# 1-Schematic_CessnaCitationX_APU.net
KiCad netlist of a schematic drawn in EasyEDA
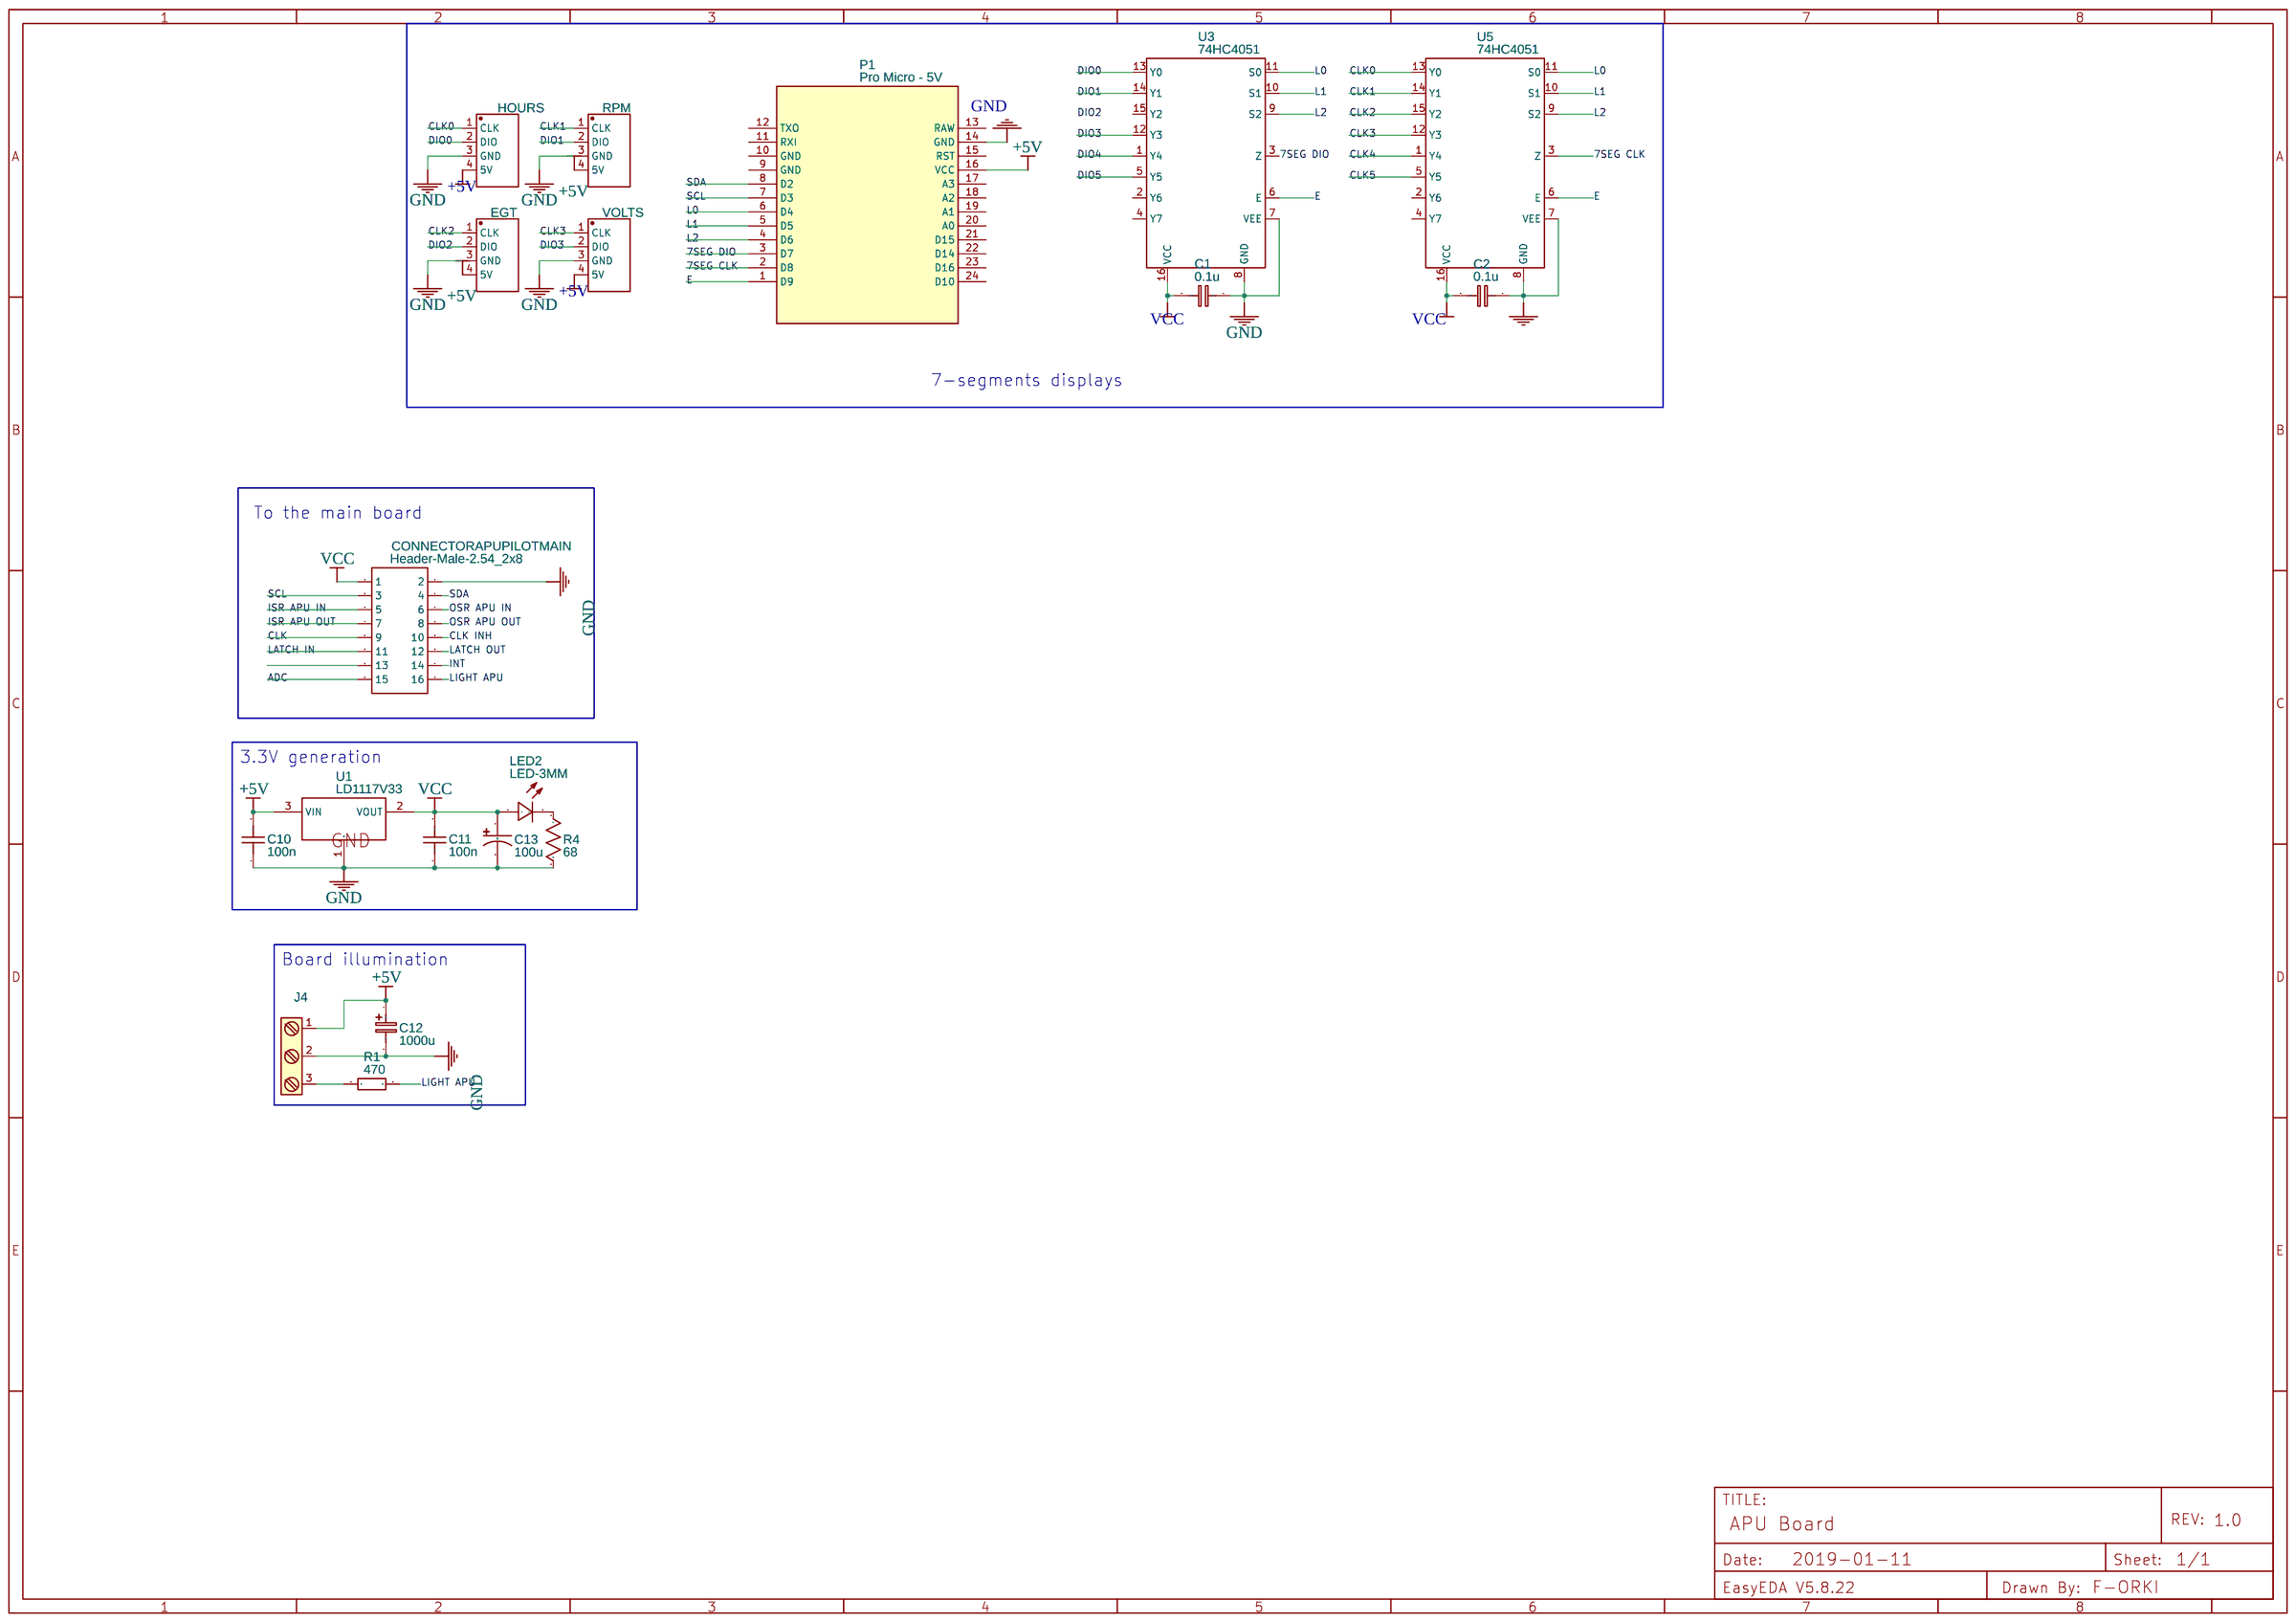
[diagram p0: schematic sheet]

(export (version "E")
  (design (tool "Eeschema 10.0.6"))
  (components
    (comp (ref "C1")
      (value "0.1u")
      (fields (field (name "BOM_Manufacturer Part") "?"))
      (libsource (lib "") (part "Cap_RAD-0.1_EU"))
    )
    (comp (ref "C2")
      (value "0.1u")
      (fields (field (name "BOM_Manufacturer Part") "?"))
      (libsource (lib "") (part "Cap_RAD-0.1_EU"))
    )
    (comp (ref "C10")
      (value "100n")
      (fields (field (name "BOM_Manufacturer Part") "?"))
      (libsource (lib "") (part "Cap_RAD-0.1_US"))
    )
    (comp (ref "C11")
      (value "100n")
      (fields (field (name "BOM_Manufacturer Part") "?"))
      (libsource (lib "") (part "Cap_RAD-0.1_US"))
    )
    (comp (ref "C12")
      (value "1000u")
      (fields (field (name "BOM_Manufacturer Part") "?"))
      (libsource (lib "") (part "Cap_Electrolytic(TH)_D3.0XF1.5_EU"))
    )
    (comp (ref "C13")
      (value "100u")
      (fields (field (name "BOM_Manufacturer Part") "?"))
      (libsource (lib "") (part "Cap_Electrolytic(TH)_D3.0XF1.5_US"))
    )
    (comp (ref "CONNECTORAPUPILOTMAIN")
      (value "Header-Male-2.54_2x8")
      (fields
        (field (name "BOM_Manufacturer Part") "Double row straight 2*8Headers  Pins 2.54mm")
        (field (name "BOM_Supplier Part") "C68234")
      )
      (libsource (lib "") (part "Unknown_280_445"))
    )
    (comp (ref "EGT")
      (value "7seg display module TM1637")
      (fields
        (field (name "BOM_Manufacturer Part") "WJ2EDGVC-5.08-4P")
        (field (name "BOM_Supplier Part") "C8471")
      )
      (libsource (lib "") (part "Unknown_340_175"))
    )
    (comp (ref "HOURS")
      (value "7seg display module TM1637")
      (fields
        (field (name "BOM_Manufacturer Part") "WJ2EDGVC-5.08-4P")
        (field (name "BOM_Supplier Part") "C8471")
      )
      (libsource (lib "") (part "Unknown_340_100"))
    )
    (comp (ref "J4")
      (value "Screw_Terminal_1x03")
      (fields (field (name "BOM_Manufacturer Part") "?"))
      (libsource (lib "") (part "Unknown_210_750"))
    )
    (comp (ref "LED2")
      (value "LED-3MM")
      (fields
        (field (name "BOM_Manufacturer Part") "204-10SURD/S530-A3")
        (field (name "BOM_Supplier Part") "C99772")
      )
      (libsource (lib "") (part "Unknown_370_570"))
    )
    (comp (ref "P1")
      (value "Pro Micro - 5V")
      (fields (field (name "BOM_Manufacturer Part") "?"))
      (libsource (lib "") (part "Unknown_615_140"))
    )
    (comp (ref "R1")
      (value "470")
      (fields (field (name "BOM_Manufacturer Part") "?"))
      (libsource (lib "") (part "Res_AXIAL-0.3(1/8W)_EU"))
    )
    (comp (ref "R4")
      (value "68")
      (fields (field (name "BOM_Manufacturer Part") "?"))
      (libsource (lib "") (part "Res_AXIAL-0.3(1/8W)_US"))
    )
    (comp (ref "RPM")
      (value "7seg display module TM1637")
      (fields
        (field (name "BOM_Manufacturer Part") "WJ2EDGVC-5.08-4P")
        (field (name "BOM_Supplier Part") "C8471")
      )
      (libsource (lib "") (part "Unknown_420_100"))
    )
    (comp (ref "U1")
      (value "LD1117V33")
      (fields (field (name "BOM_Supplier Part") "C283467"))
      (libsource (lib "") (part "Unknown_240_595"))
    )
    (comp (ref "U3")
      (value "74HC4051")
      (fields (field (name "BOM_Manufacturer Part") "?"))
      (libsource (lib "") (part "Unknown_860_105"))
    )
    (comp (ref "U5")
      (value "74HC4051")
      (fields (field (name "BOM_Manufacturer Part") "?"))
      (libsource (lib "") (part "Unknown_1060_105"))
    )
    (comp (ref "VOLTS")
      (value "7seg display module TM1637")
      (fields
        (field (name "BOM_Manufacturer Part") "WJ2EDGVC-5.08-4P")
        (field (name "BOM_Supplier Part") "C8471")
      )
      (libsource (lib "") (part "Unknown_420_175"))
    )
  )
  (nets
    (net (code "1") (name "+5V") (class "Default")
      (node (ref "C10") (pin "2") (pinfunction "2_2") (pintype "unspecified"))
      (node (ref "C12") (pin "1") (pinfunction "1_1") (pintype "unspecified"))
      (node (ref "EGT") (pin "4") (pinfunction "5V_4") (pintype "unspecified"))
      (node (ref "HOURS") (pin "4") (pinfunction "5V_4") (pintype "unspecified"))
      (node (ref "J4") (pin "1") (pintype "unspecified"))
      (node (ref "P1") (pin "16") (pinfunction "VCC_16") (pintype "unspecified"))
      (node (ref "RPM") (pin "4") (pinfunction "5V_4") (pintype "unspecified"))
      (node (ref "U1") (pin "3") (pinfunction "VIN_3") (pintype "passive"))
      (node (ref "VOLTS") (pin "4") (pinfunction "5V_4") (pintype "unspecified"))
    )
    (net (code "2") (name "/7SEG CLK") (class "Default")
      (node (ref "P1") (pin "2") (pinfunction "D8_2") (pintype "unspecified"))
      (node (ref "U5") (pin "3") (pinfunction "Z_3") (pintype "unspecified"))
    )
    (net (code "3") (name "/7SEG DIO") (class "Default")
      (node (ref "P1") (pin "3") (pinfunction "D7_3") (pintype "unspecified"))
      (node (ref "U3") (pin "3") (pinfunction "Z_3") (pintype "unspecified"))
    )
    (net (code "4") (name "/ADC") (class "Default")
      (node (ref "CONNECTORAPUPILOTMAIN") (pin "15") (pinfunction "15_15") (pintype "input"))
    )
    (net (code "5") (name "/CLK") (class "Default")
      (node (ref "CONNECTORAPUPILOTMAIN") (pin "9") (pinfunction "9_9") (pintype "input"))
    )
    (net (code "6") (name "/CLK INH") (class "Default")
      (node (ref "CONNECTORAPUPILOTMAIN") (pin "10") (pinfunction "10_10") (pintype "input"))
    )
    (net (code "7") (name "/CLK0") (class "Default")
      (node (ref "HOURS") (pin "1") (pinfunction "CLK_1") (pintype "unspecified"))
      (node (ref "U5") (pin "13") (pinfunction "Y0_13") (pintype "unspecified"))
    )
    (net (code "8") (name "/CLK1") (class "Default")
      (node (ref "RPM") (pin "1") (pinfunction "CLK_1") (pintype "unspecified"))
      (node (ref "U5") (pin "14") (pinfunction "Y1_14") (pintype "unspecified"))
    )
    (net (code "9") (name "/CLK2") (class "Default")
      (node (ref "EGT") (pin "1") (pinfunction "CLK_1") (pintype "unspecified"))
      (node (ref "U5") (pin "15") (pinfunction "Y2_15") (pintype "unspecified"))
    )
    (net (code "10") (name "/CLK3") (class "Default")
      (node (ref "U5") (pin "12") (pinfunction "Y3_12") (pintype "unspecified"))
      (node (ref "VOLTS") (pin "1") (pinfunction "CLK_1") (pintype "unspecified"))
    )
    (net (code "11") (name "/CLK4") (class "Default")
      (node (ref "U5") (pin "1") (pinfunction "Y4_1") (pintype "unspecified"))
    )
    (net (code "12") (name "/CLK5") (class "Default")
      (node (ref "U5") (pin "5") (pinfunction "Y5_5") (pintype "unspecified"))
    )
    (net (code "13") (name "/DIO0") (class "Default")
      (node (ref "HOURS") (pin "2") (pinfunction "DIO_2") (pintype "unspecified"))
      (node (ref "U3") (pin "13") (pinfunction "Y0_13") (pintype "unspecified"))
    )
    (net (code "14") (name "/DIO1") (class "Default")
      (node (ref "RPM") (pin "2") (pinfunction "DIO_2") (pintype "unspecified"))
      (node (ref "U3") (pin "14") (pinfunction "Y1_14") (pintype "unspecified"))
    )
    (net (code "15") (name "/DIO2") (class "Default")
      (node (ref "EGT") (pin "2") (pinfunction "DIO_2") (pintype "unspecified"))
    )
    (net (code "16") (name "/DIO3") (class "Default")
      (node (ref "U3") (pin "12") (pinfunction "Y3_12") (pintype "unspecified"))
      (node (ref "VOLTS") (pin "2") (pinfunction "DIO_2") (pintype "unspecified"))
    )
    (net (code "17") (name "/DIO4") (class "Default")
      (node (ref "U3") (pin "1") (pinfunction "Y4_1") (pintype "unspecified"))
    )
    (net (code "18") (name "/DIO5") (class "Default")
      (node (ref "U3") (pin "5") (pinfunction "Y5_5") (pintype "unspecified"))
    )
    (net (code "19") (name "/E") (class "Default")
      (node (ref "P1") (pin "1") (pinfunction "D9_1") (pintype "unspecified"))
      (node (ref "U3") (pin "6") (pinfunction "E_6") (pintype "unspecified"))
      (node (ref "U5") (pin "6") (pinfunction "E_6") (pintype "unspecified"))
    )
    (net (code "20") (name "/INT") (class "Default")
      (node (ref "CONNECTORAPUPILOTMAIN") (pin "14") (pinfunction "14_14") (pintype "input"))
    )
    (net (code "21") (name "/ISR APU IN") (class "Default")
      (node (ref "CONNECTORAPUPILOTMAIN") (pin "5") (pinfunction "5_5") (pintype "input"))
    )
    (net (code "22") (name "/ISR APU OUT") (class "Default")
      (node (ref "CONNECTORAPUPILOTMAIN") (pin "7") (pinfunction "7_7") (pintype "input"))
    )
    (net (code "23") (name "/L0") (class "Default")
      (node (ref "P1") (pin "6") (pinfunction "D4_6") (pintype "unspecified"))
      (node (ref "U3") (pin "11") (pinfunction "S0_11") (pintype "unspecified"))
      (node (ref "U5") (pin "11") (pinfunction "S0_11") (pintype "unspecified"))
    )
    (net (code "24") (name "/L1") (class "Default")
      (node (ref "P1") (pin "5") (pinfunction "D5_5") (pintype "unspecified"))
      (node (ref "U3") (pin "10") (pinfunction "S1_10") (pintype "unspecified"))
      (node (ref "U5") (pin "10") (pinfunction "S1_10") (pintype "unspecified"))
    )
    (net (code "25") (name "/L2") (class "Default")
      (node (ref "P1") (pin "4") (pinfunction "D6_4") (pintype "unspecified"))
      (node (ref "U3") (pin "9") (pinfunction "S2_9") (pintype "unspecified"))
      (node (ref "U5") (pin "9") (pinfunction "S2_9") (pintype "unspecified"))
    )
    (net (code "26") (name "/LATCH IN") (class "Default")
      (node (ref "CONNECTORAPUPILOTMAIN") (pin "11") (pinfunction "11_11") (pintype "input"))
    )
    (net (code "27") (name "/LATCH OUT") (class "Default")
      (node (ref "CONNECTORAPUPILOTMAIN") (pin "12") (pinfunction "12_12") (pintype "input"))
    )
    (net (code "28") (name "/LIGHT APU") (class "Default")
      (node (ref "CONNECTORAPUPILOTMAIN") (pin "16") (pinfunction "16_16") (pintype "input"))
      (node (ref "R1") (pin "2") (pinfunction "2_2") (pintype "unspecified"))
    )
    (net (code "29") (name "/OSR APU IN") (class "Default")
      (node (ref "CONNECTORAPUPILOTMAIN") (pin "6") (pinfunction "6_6") (pintype "input"))
    )
    (net (code "30") (name "/OSR APU OUT") (class "Default")
      (node (ref "CONNECTORAPUPILOTMAIN") (pin "8") (pinfunction "8_8") (pintype "input"))
    )
    (net (code "31") (name "/SCL") (class "Default")
      (node (ref "CONNECTORAPUPILOTMAIN") (pin "3") (pinfunction "3_3") (pintype "input"))
      (node (ref "P1") (pin "7") (pinfunction "D3_7") (pintype "unspecified"))
    )
    (net (code "32") (name "/SDA") (class "Default")
      (node (ref "CONNECTORAPUPILOTMAIN") (pin "4") (pinfunction "4_4") (pintype "input"))
      (node (ref "P1") (pin "8") (pinfunction "D2_8") (pintype "unspecified"))
    )
    (net (code "33") (name "GND") (class "Default")
      (node (ref "C1") (pin "1") (pinfunction "1_1") (pintype "unspecified"))
      (node (ref "C10") (pin "1") (pinfunction "1_1") (pintype "unspecified"))
      (node (ref "C11") (pin "1") (pinfunction "1_1") (pintype "unspecified"))
      (node (ref "C12") (pin "2") (pinfunction "2_2") (pintype "unspecified"))
      (node (ref "C13") (pin "2") (pinfunction "2_2") (pintype "unspecified"))
      (node (ref "C2") (pin "1") (pinfunction "1_1") (pintype "unspecified"))
      (node (ref "CONNECTORAPUPILOTMAIN") (pin "2") (pinfunction "2_2") (pintype "input"))
      (node (ref "EGT") (pin "3") (pinfunction "GND_3") (pintype "unspecified"))
      (node (ref "HOURS") (pin "3") (pinfunction "GND_3") (pintype "unspecified"))
      (node (ref "J4") (pin "2") (pintype "unspecified"))
      (node (ref "P1") (pin "14") (pinfunction "GND_14") (pintype "unspecified"))
      (node (ref "R4") (pin "2") (pinfunction "2_2") (pintype "unspecified"))
      (node (ref "RPM") (pin "3") (pinfunction "GND_3") (pintype "unspecified"))
      (node (ref "U1") (pin "1") (pinfunction "GND_1") (pintype "unspecified"))
      (node (ref "U3") (pin "7") (pinfunction "VEE_7") (pintype "unspecified"))
      (node (ref "U3") (pin "8") (pinfunction "GND_8") (pintype "unspecified"))
      (node (ref "U5") (pin "7") (pinfunction "VEE_7") (pintype "unspecified"))
      (node (ref "U5") (pin "8") (pinfunction "GND_8") (pintype "unspecified"))
      (node (ref "VOLTS") (pin "3") (pinfunction "GND_3") (pintype "unspecified"))
    )
    (net (code "34") (name "Net-(J4-Pad3)") (class "Default")
      (node (ref "J4") (pin "3") (pintype "unspecified"))
      (node (ref "R1") (pin "1") (pinfunction "1_1") (pintype "unspecified"))
    )
    (net (code "35") (name "Net-(LED2--)") (class "Default")
      (node (ref "LED2") (pin "2") (pinfunction "-_2") (pintype "unspecified"))
      (node (ref "R4") (pin "1") (pinfunction "1_1") (pintype "unspecified"))
    )
    (net (code "36") (name "VCC") (class "Default")
      (node (ref "C1") (pin "2") (pinfunction "2_2") (pintype "unspecified"))
      (node (ref "C11") (pin "2") (pinfunction "2_2") (pintype "unspecified"))
      (node (ref "C13") (pin "1") (pinfunction "1_1") (pintype "unspecified"))
      (node (ref "C2") (pin "2") (pinfunction "2_2") (pintype "unspecified"))
      (node (ref "CONNECTORAPUPILOTMAIN") (pin "1") (pinfunction "1_1") (pintype "input"))
      (node (ref "LED2") (pin "1") (pinfunction "+_1") (pintype "unspecified"))
      (node (ref "U1") (pin "2") (pinfunction "VOUT_2") (pintype "passive"))
      (node (ref "U3") (pin "16") (pinfunction "VCC_16") (pintype "unspecified"))
      (node (ref "U5") (pin "16") (pinfunction "VCC_16") (pintype "unspecified"))
    )
    (net (code "37") (name "unconnected-(CONNECTORAPUPILOTMAIN-Pad13)") (class "Default")
      (node (ref "CONNECTORAPUPILOTMAIN") (pin "13") (pinfunction "13_13") (pintype "input"))
    )
    (net (code "38") (name "unconnected-(P1-A0-Pad20)") (class "Default")
      (node (ref "P1") (pin "20") (pinfunction "A0_20") (pintype "unspecified"))
    )
    (net (code "39") (name "unconnected-(P1-A1-Pad19)") (class "Default")
      (node (ref "P1") (pin "19") (pinfunction "A1_19") (pintype "unspecified"))
    )
    (net (code "40") (name "unconnected-(P1-A2-Pad18)") (class "Default")
      (node (ref "P1") (pin "18") (pinfunction "A2_18") (pintype "unspecified"))
    )
    (net (code "41") (name "unconnected-(P1-A3-Pad17)") (class "Default")
      (node (ref "P1") (pin "17") (pinfunction "A3_17") (pintype "unspecified"))
    )
    (net (code "42") (name "unconnected-(P1-D10-Pad24)") (class "Default")
      (node (ref "P1") (pin "24") (pinfunction "D10_24") (pintype "unspecified"))
    )
    (net (code "43") (name "unconnected-(P1-D14-Pad22)") (class "Default")
      (node (ref "P1") (pin "22") (pinfunction "D14_22") (pintype "unspecified"))
    )
    (net (code "44") (name "unconnected-(P1-D15-Pad21)") (class "Default")
      (node (ref "P1") (pin "21") (pinfunction "D15_21") (pintype "unspecified"))
    )
    (net (code "45") (name "unconnected-(P1-D16-Pad23)") (class "Default")
      (node (ref "P1") (pin "23") (pinfunction "D16_23") (pintype "unspecified"))
    )
    (net (code "46") (name "unconnected-(P1-GND-Pad9)") (class "Default")
      (node (ref "P1") (pin "9") (pinfunction "GND_9") (pintype "unspecified"))
    )
    (net (code "47") (name "unconnected-(P1-GND-Pad10)") (class "Default")
      (node (ref "P1") (pin "10") (pinfunction "GND_10") (pintype "unspecified"))
    )
    (net (code "48") (name "unconnected-(P1-RAW-Pad13)") (class "Default")
      (node (ref "P1") (pin "13") (pinfunction "RAW_13") (pintype "unspecified"))
    )
    (net (code "49") (name "unconnected-(P1-RST-Pad15)") (class "Default")
      (node (ref "P1") (pin "15") (pinfunction "RST_15") (pintype "unspecified"))
    )
    (net (code "50") (name "unconnected-(P1-RXI-Pad11)") (class "Default")
      (node (ref "P1") (pin "11") (pinfunction "RXI_11") (pintype "unspecified"))
    )
    (net (code "51") (name "unconnected-(P1-TXO-Pad12)") (class "Default")
      (node (ref "P1") (pin "12") (pinfunction "TXO_12") (pintype "unspecified"))
    )
    (net (code "52") (name "unconnected-(U3-Y2-Pad15)") (class "Default")
      (node (ref "U3") (pin "15") (pinfunction "Y2_15") (pintype "unspecified"))
    )
    (net (code "53") (name "unconnected-(U3-Y6-Pad2)") (class "Default")
      (node (ref "U3") (pin "2") (pinfunction "Y6_2") (pintype "unspecified"))
    )
    (net (code "54") (name "unconnected-(U3-Y7-Pad4)") (class "Default")
      (node (ref "U3") (pin "4") (pinfunction "Y7_4") (pintype "unspecified"))
    )
    (net (code "55") (name "unconnected-(U5-Y6-Pad2)") (class "Default")
      (node (ref "U5") (pin "2") (pinfunction "Y6_2") (pintype "unspecified"))
    )
    (net (code "56") (name "unconnected-(U5-Y7-Pad4)") (class "Default")
      (node (ref "U5") (pin "4") (pinfunction "Y7_4") (pintype "unspecified"))
    )
  )
)
